# Environment-ArduinoNano44-Mini-Enclosure.net
KiCad netlist of a schematic drawn in EAGLE
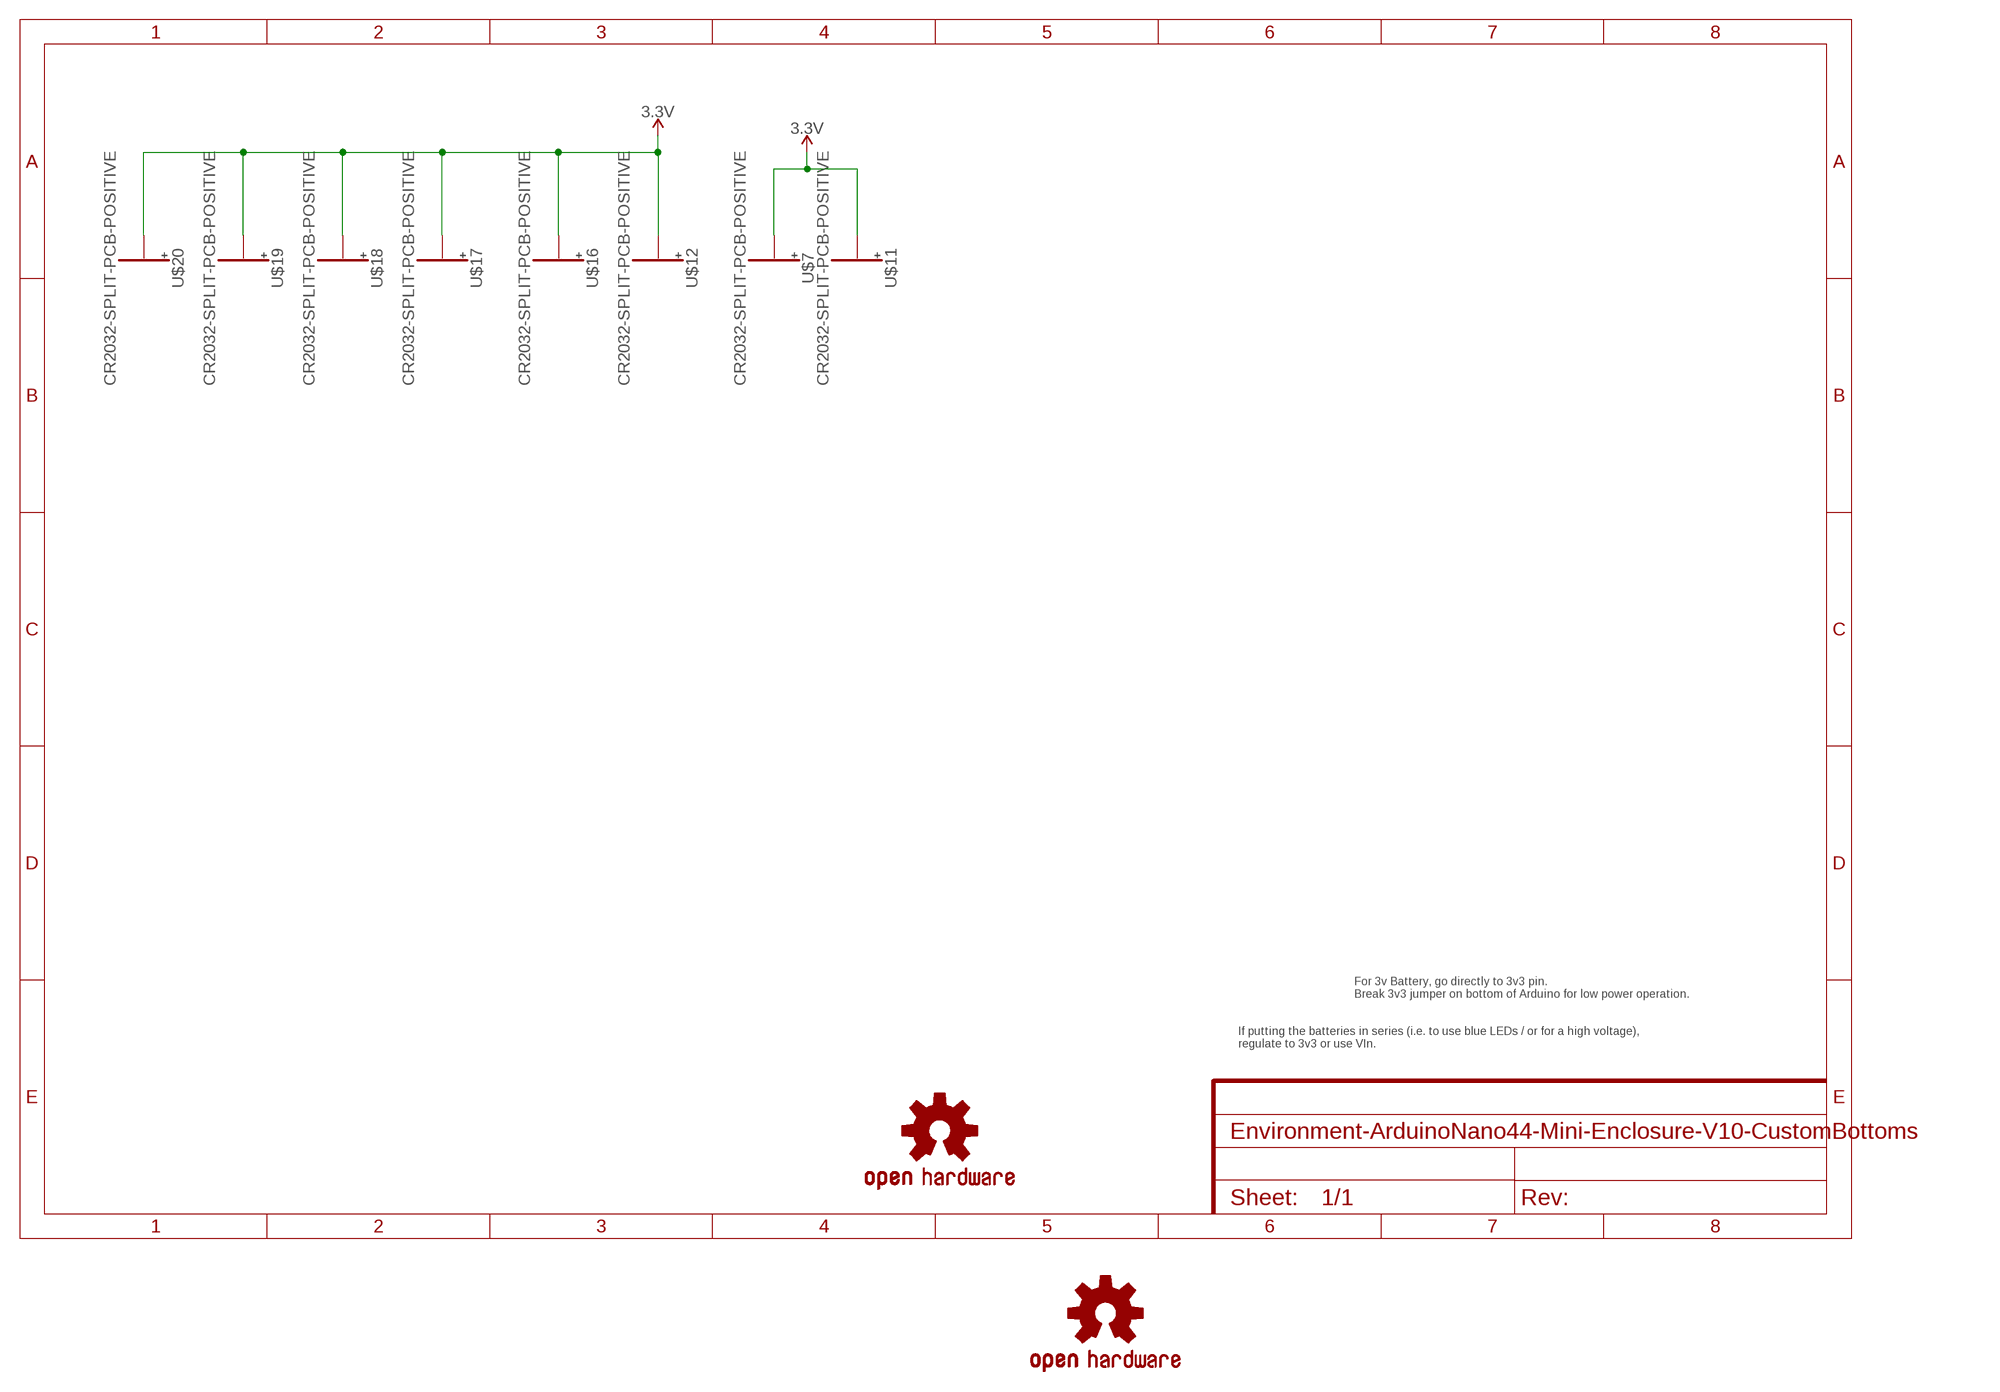
[diagram p0: schematic, sheet 1]

(export (version "E")
  (design (tool "Eeschema 10.0.6"))
  (components
    (comp (ref "LOGO2")
      (value "OSHW-LOGOL")
      (footprint "eagle-import:OSHW-LOGO-L")
      (libsource (lib "eagle-import") (part "OSHW-LOGOL"))
    )
    (comp (ref "LOGO7")
      (value "OSHW-LOGOM")
      (footprint "eagle-import:OSHW-LOGO-M")
      (libsource (lib "eagle-import") (part "OSHW-LOGOM"))
    )
    (comp (ref "U$7")
      (value "CR2032-SPLIT-PCB-POSITIVE")
      (footprint "eagle-import:CR2032-SMD-POSITIVE-TERMINAL")
      (libsource (lib "eagle-import") (part "CR2032-SPLIT-PCB-POSITIVE"))
    )
    (comp (ref "U$11")
      (value "CR2032-SPLIT-PCB-POSITIVE")
      (footprint "eagle-import:CR2032-SMD-POSITIVE-TERMINAL")
      (libsource (lib "eagle-import") (part "CR2032-SPLIT-PCB-POSITIVE"))
    )
    (comp (ref "U$12")
      (value "CR2032-SPLIT-PCB-POSITIVE")
      (footprint "eagle-import:CR2032-SMD-POSITIVE-TERMINAL")
      (libsource (lib "eagle-import") (part "CR2032-SPLIT-PCB-POSITIVE"))
    )
    (comp (ref "U$16")
      (value "CR2032-SPLIT-PCB-POSITIVE")
      (footprint "eagle-import:CR2032-SMD-POSITIVE-TERMINAL")
      (libsource (lib "eagle-import") (part "CR2032-SPLIT-PCB-POSITIVE"))
    )
    (comp (ref "U$17")
      (value "CR2032-SPLIT-PCB-POSITIVE")
      (footprint "eagle-import:CR2032-SMD-POSITIVE-TERMINAL")
      (libsource (lib "eagle-import") (part "CR2032-SPLIT-PCB-POSITIVE"))
    )
    (comp (ref "U$18")
      (value "CR2032-SPLIT-PCB-POSITIVE")
      (footprint "eagle-import:CR2032-SMD-POSITIVE-TERMINAL")
      (libsource (lib "eagle-import") (part "CR2032-SPLIT-PCB-POSITIVE"))
    )
    (comp (ref "U$19")
      (value "CR2032-SPLIT-PCB-POSITIVE")
      (footprint "eagle-import:CR2032-SMD-POSITIVE-TERMINAL")
      (libsource (lib "eagle-import") (part "CR2032-SPLIT-PCB-POSITIVE"))
    )
    (comp (ref "U$20")
      (value "CR2032-SPLIT-PCB-POSITIVE")
      (footprint "eagle-import:CR2032-SMD-POSITIVE-TERMINAL")
      (libsource (lib "eagle-import") (part "CR2032-SPLIT-PCB-POSITIVE"))
    )
  )
  (nets
    (net (code "1") (name "3.3V") (class "Default")
      (node (ref "U$11") (pin "+") (pinfunction "+_+") (pintype "power_in"))
      (node (ref "U$12") (pin "+") (pinfunction "+_+") (pintype "power_in"))
      (node (ref "U$16") (pin "+") (pinfunction "+_+") (pintype "power_in"))
      (node (ref "U$17") (pin "+") (pinfunction "+_+") (pintype "power_in"))
      (node (ref "U$18") (pin "+") (pinfunction "+_+") (pintype "power_in"))
      (node (ref "U$19") (pin "+") (pinfunction "+_+") (pintype "power_in"))
      (node (ref "U$20") (pin "+") (pinfunction "+_+") (pintype "power_in"))
      (node (ref "U$7") (pin "+") (pinfunction "+_+") (pintype "power_in"))
    )
  )
)
